# PCB_LEDs_GPIO_servicios_2021-05-17.net
KiCad netlist of a schematic drawn in EasyEDA
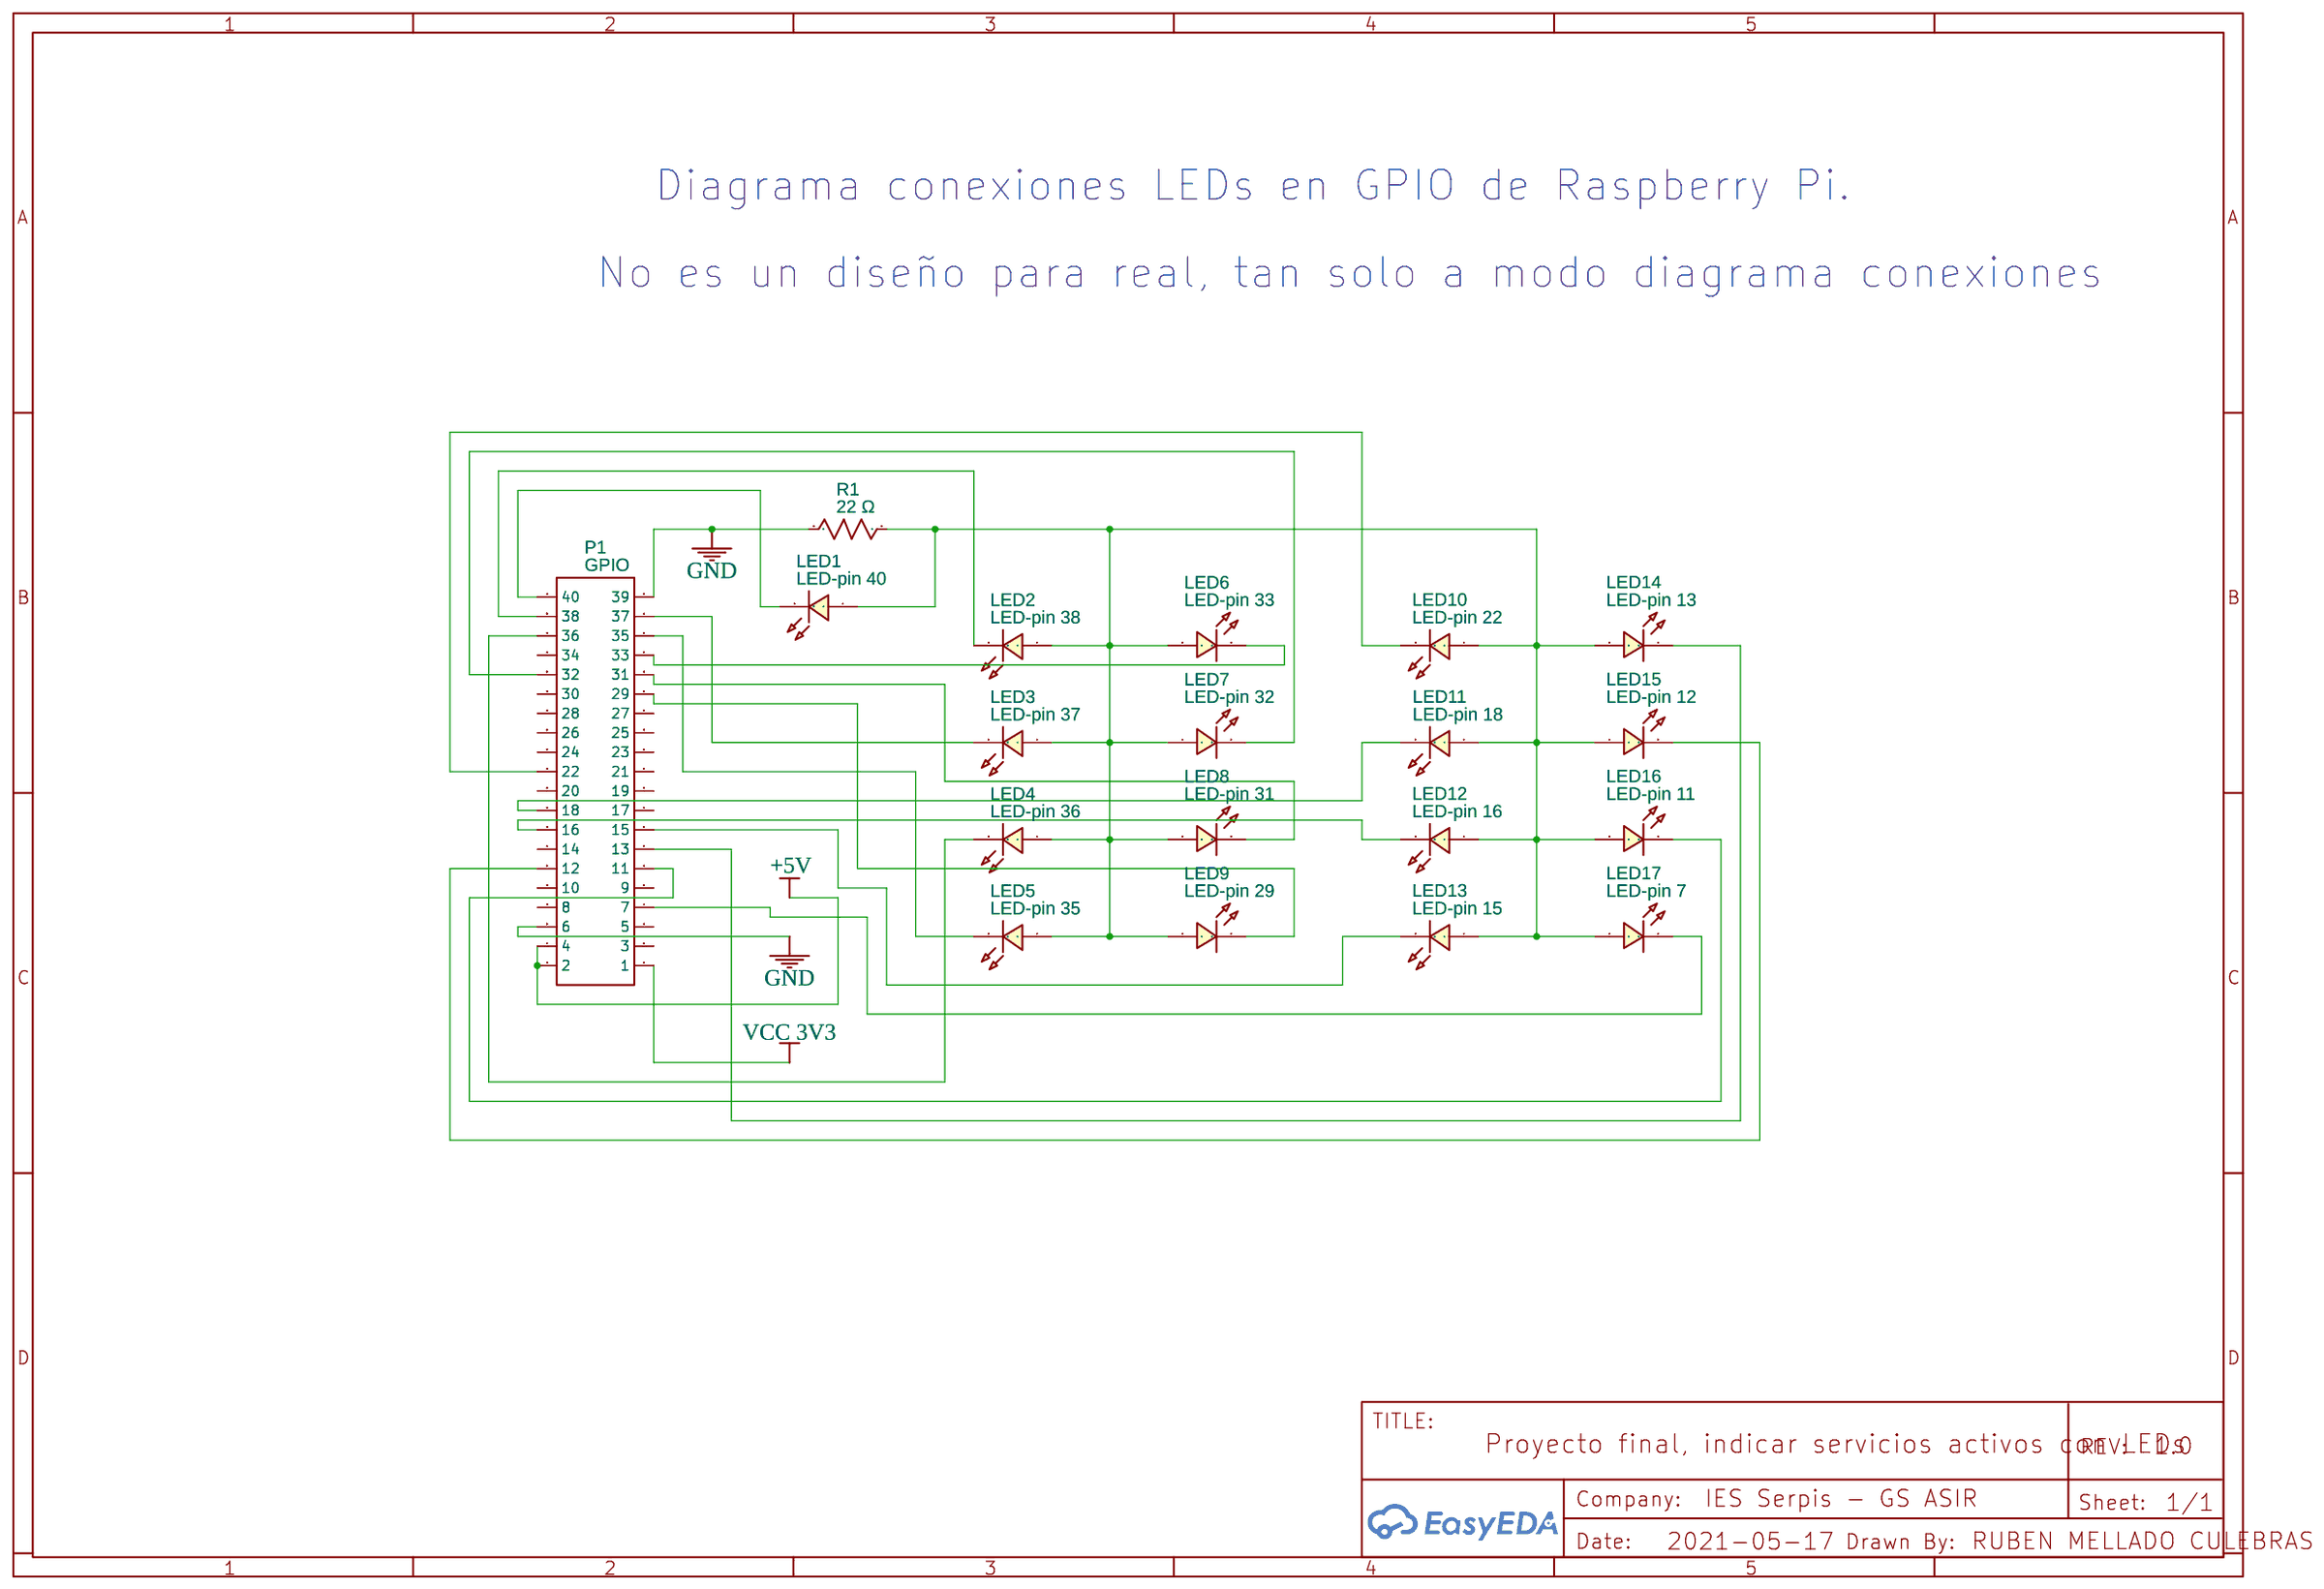
[diagram p0: schematic sheet]

(export (version "E")
  (design (tool "Eeschema 10.0.6"))
  (components
    (comp (ref "LED1")
      (value "LED-pin 40")
      (fields
        (field (name "BOM_Manufacturer Part") "19-217/R6C-AL1M2VY/3T")
        (field (name "BOM_Supplier Part") "C72044")
      )
      (libsource (lib "") (part "LED-0603_R_1"))
    )
    (comp (ref "LED2")
      (value "LED-pin 38")
      (fields
        (field (name "BOM_Manufacturer Part") "19-217/R6C-AL1M2VY/3T")
        (field (name "BOM_Supplier Part") "C72044")
      )
      (libsource (lib "") (part "LED-0603_R_1"))
    )
    (comp (ref "LED3")
      (value "LED-pin 37")
      (fields
        (field (name "BOM_Manufacturer Part") "19-217/R6C-AL1M2VY/3T")
        (field (name "BOM_Supplier Part") "C72044")
      )
      (libsource (lib "") (part "LED-0603_R_1"))
    )
    (comp (ref "LED4")
      (value "LED-pin 36")
      (fields
        (field (name "BOM_Manufacturer Part") "19-217/R6C-AL1M2VY/3T")
        (field (name "BOM_Supplier Part") "C72044")
      )
      (libsource (lib "") (part "LED-0603_R_1"))
    )
    (comp (ref "LED5")
      (value "LED-pin 35")
      (fields
        (field (name "BOM_Manufacturer Part") "19-217/R6C-AL1M2VY/3T")
        (field (name "BOM_Supplier Part") "C72044")
      )
      (libsource (lib "") (part "LED-0603_R_1"))
    )
    (comp (ref "LED6")
      (value "LED-pin 33")
      (fields
        (field (name "BOM_Manufacturer Part") "19-217/R6C-AL1M2VY/3T")
        (field (name "BOM_Supplier Part") "C72044")
      )
      (libsource (lib "") (part "LED-0603_R"))
    )
    (comp (ref "LED7")
      (value "LED-pin 32")
      (fields
        (field (name "BOM_Manufacturer Part") "19-217/R6C-AL1M2VY/3T")
        (field (name "BOM_Supplier Part") "C72044")
      )
      (libsource (lib "") (part "LED-0603_R"))
    )
    (comp (ref "LED8")
      (value "LED-pin 31")
      (fields
        (field (name "BOM_Manufacturer Part") "19-217/R6C-AL1M2VY/3T")
        (field (name "BOM_Supplier Part") "C72044")
      )
      (libsource (lib "") (part "LED-0603_R"))
    )
    (comp (ref "LED9")
      (value "LED-pin 29")
      (fields
        (field (name "BOM_Manufacturer Part") "19-217/R6C-AL1M2VY/3T")
        (field (name "BOM_Supplier Part") "C72044")
      )
      (libsource (lib "") (part "LED-0603_R"))
    )
    (comp (ref "LED10")
      (value "LED-pin 22")
      (fields
        (field (name "BOM_Manufacturer Part") "19-217/R6C-AL1M2VY/3T")
        (field (name "BOM_Supplier Part") "C72044")
      )
      (libsource (lib "") (part "LED-0603_R_1"))
    )
    (comp (ref "LED11")
      (value "LED-pin 18")
      (fields
        (field (name "BOM_Manufacturer Part") "19-217/R6C-AL1M2VY/3T")
        (field (name "BOM_Supplier Part") "C72044")
      )
      (libsource (lib "") (part "LED-0603_R_1"))
    )
    (comp (ref "LED12")
      (value "LED-pin 16")
      (fields
        (field (name "BOM_Manufacturer Part") "19-217/R6C-AL1M2VY/3T")
        (field (name "BOM_Supplier Part") "C72044")
      )
      (libsource (lib "") (part "LED-0603_R_1"))
    )
    (comp (ref "LED13")
      (value "LED-pin 15")
      (fields
        (field (name "BOM_Manufacturer Part") "19-217/R6C-AL1M2VY/3T")
        (field (name "BOM_Supplier Part") "C72044")
      )
      (libsource (lib "") (part "LED-0603_R_1"))
    )
    (comp (ref "LED14")
      (value "LED-pin 13")
      (fields
        (field (name "BOM_Manufacturer Part") "19-217/R6C-AL1M2VY/3T")
        (field (name "BOM_Supplier Part") "C72044")
      )
      (libsource (lib "") (part "LED-0603_R"))
    )
    (comp (ref "LED15")
      (value "LED-pin 12")
      (fields
        (field (name "BOM_Manufacturer Part") "19-217/R6C-AL1M2VY/3T")
        (field (name "BOM_Supplier Part") "C72044")
      )
      (libsource (lib "") (part "LED-0603_R"))
    )
    (comp (ref "LED16")
      (value "LED-pin 11")
      (fields
        (field (name "BOM_Manufacturer Part") "19-217/R6C-AL1M2VY/3T")
        (field (name "BOM_Supplier Part") "C72044")
      )
      (libsource (lib "") (part "LED-0603_R"))
    )
    (comp (ref "LED17")
      (value "LED-pin 7")
      (fields
        (field (name "BOM_Manufacturer Part") "19-217/R6C-AL1M2VY/3T")
        (field (name "BOM_Supplier Part") "C72044")
      )
      (libsource (lib "") (part "LED-0603_R"))
    )
    (comp (ref "P1")
      (value "GPIO")
      (fields
        (field (name "BOM_Manufacturer Part") "IDC Box 2X20 2.54MM")
        (field (name "BOM_Supplier Part") "C9138")
      )
      (libsource (lib "") (part "HDR-IDC-2.54-2X20P"))
    )
    (comp (ref "R1") (value "22 Ω") (libsource (lib "") (part "R_0603_US")))
  )
  (nets
    (net (code "1") (name "+5V") (class "Default")
      (node (ref "P1") (pin "2") (pinfunction "2_2") (pintype "unspecified"))
      (node (ref "P1") (pin "4") (pinfunction "4_4") (pintype "unspecified"))
    )
    (net (code "2") (name "GND") (class "Default")
      (node (ref "P1") (pin "39") (pinfunction "39_39") (pintype "unspecified"))
      (node (ref "P1") (pin "6") (pinfunction "6_6") (pintype "unspecified"))
      (node (ref "R1") (pin "1") (pinfunction "1_1") (pintype "unspecified"))
    )
    (net (code "3") (name "Net-(LED1-Pad1)") (class "Default")
      (node (ref "LED1") (pin "1") (pinfunction "1_1") (pintype "unspecified"))
      (node (ref "LED10") (pin "1") (pinfunction "1_1") (pintype "unspecified"))
      (node (ref "LED11") (pin "1") (pinfunction "1_1") (pintype "unspecified"))
      (node (ref "LED12") (pin "1") (pinfunction "1_1") (pintype "unspecified"))
      (node (ref "LED13") (pin "1") (pinfunction "1_1") (pintype "unspecified"))
      (node (ref "LED14") (pin "1") (pinfunction "1_1") (pintype "unspecified"))
      (node (ref "LED15") (pin "1") (pinfunction "1_1") (pintype "unspecified"))
      (node (ref "LED16") (pin "1") (pinfunction "1_1") (pintype "unspecified"))
      (node (ref "LED17") (pin "1") (pinfunction "1_1") (pintype "unspecified"))
      (node (ref "LED2") (pin "1") (pinfunction "1_1") (pintype "unspecified"))
      (node (ref "LED3") (pin "1") (pinfunction "1_1") (pintype "unspecified"))
      (node (ref "LED4") (pin "1") (pinfunction "1_1") (pintype "unspecified"))
      (node (ref "LED5") (pin "1") (pinfunction "1_1") (pintype "unspecified"))
      (node (ref "LED6") (pin "1") (pinfunction "1_1") (pintype "unspecified"))
      (node (ref "LED7") (pin "1") (pinfunction "1_1") (pintype "unspecified"))
      (node (ref "LED8") (pin "1") (pinfunction "1_1") (pintype "unspecified"))
      (node (ref "LED9") (pin "1") (pinfunction "1_1") (pintype "unspecified"))
      (node (ref "R1") (pin "2") (pinfunction "2_2") (pintype "unspecified"))
    )
    (net (code "4") (name "Net-(LED1-Pad2)") (class "Default")
      (node (ref "LED1") (pin "2") (pinfunction "2_2") (pintype "unspecified"))
      (node (ref "P1") (pin "40") (pinfunction "40_40") (pintype "unspecified"))
    )
    (net (code "5") (name "Net-(LED2-Pad2)") (class "Default")
      (node (ref "LED2") (pin "2") (pinfunction "2_2") (pintype "unspecified"))
      (node (ref "P1") (pin "38") (pinfunction "38_38") (pintype "unspecified"))
    )
    (net (code "6") (name "Net-(LED3-Pad2)") (class "Default")
      (node (ref "LED3") (pin "2") (pinfunction "2_2") (pintype "unspecified"))
      (node (ref "P1") (pin "37") (pinfunction "37_37") (pintype "unspecified"))
    )
    (net (code "7") (name "Net-(LED4-Pad2)") (class "Default")
      (node (ref "LED4") (pin "2") (pinfunction "2_2") (pintype "unspecified"))
      (node (ref "P1") (pin "36") (pinfunction "36_36") (pintype "unspecified"))
    )
    (net (code "8") (name "Net-(LED5-Pad2)") (class "Default")
      (node (ref "LED5") (pin "2") (pinfunction "2_2") (pintype "unspecified"))
      (node (ref "P1") (pin "35") (pinfunction "35_35") (pintype "unspecified"))
    )
    (net (code "9") (name "Net-(LED6-Pad2)") (class "Default")
      (node (ref "LED6") (pin "2") (pinfunction "2_2") (pintype "unspecified"))
      (node (ref "P1") (pin "33") (pinfunction "33_33") (pintype "unspecified"))
    )
    (net (code "10") (name "Net-(LED7-Pad2)") (class "Default")
      (node (ref "LED7") (pin "2") (pinfunction "2_2") (pintype "unspecified"))
      (node (ref "P1") (pin "32") (pinfunction "32_32") (pintype "unspecified"))
    )
    (net (code "11") (name "Net-(LED8-Pad2)") (class "Default")
      (node (ref "LED8") (pin "2") (pinfunction "2_2") (pintype "unspecified"))
      (node (ref "P1") (pin "31") (pinfunction "31_31") (pintype "unspecified"))
    )
    (net (code "12") (name "Net-(LED9-Pad2)") (class "Default")
      (node (ref "LED9") (pin "2") (pinfunction "2_2") (pintype "unspecified"))
      (node (ref "P1") (pin "29") (pinfunction "29_29") (pintype "unspecified"))
    )
    (net (code "13") (name "Net-(LED10-Pad2)") (class "Default")
      (node (ref "LED10") (pin "2") (pinfunction "2_2") (pintype "unspecified"))
      (node (ref "P1") (pin "22") (pinfunction "22_22") (pintype "unspecified"))
    )
    (net (code "14") (name "Net-(LED11-Pad2)") (class "Default")
      (node (ref "LED11") (pin "2") (pinfunction "2_2") (pintype "unspecified"))
      (node (ref "P1") (pin "18") (pinfunction "18_18") (pintype "unspecified"))
    )
    (net (code "15") (name "Net-(LED12-Pad2)") (class "Default")
      (node (ref "LED12") (pin "2") (pinfunction "2_2") (pintype "unspecified"))
      (node (ref "P1") (pin "16") (pinfunction "16_16") (pintype "unspecified"))
    )
    (net (code "16") (name "Net-(LED13-Pad2)") (class "Default")
      (node (ref "LED13") (pin "2") (pinfunction "2_2") (pintype "unspecified"))
      (node (ref "P1") (pin "15") (pinfunction "15_15") (pintype "unspecified"))
    )
    (net (code "17") (name "Net-(LED14-Pad2)") (class "Default")
      (node (ref "LED14") (pin "2") (pinfunction "2_2") (pintype "unspecified"))
      (node (ref "P1") (pin "13") (pinfunction "13_13") (pintype "unspecified"))
    )
    (net (code "18") (name "Net-(LED15-Pad2)") (class "Default")
      (node (ref "LED15") (pin "2") (pinfunction "2_2") (pintype "unspecified"))
      (node (ref "P1") (pin "12") (pinfunction "12_12") (pintype "unspecified"))
    )
    (net (code "19") (name "Net-(LED16-Pad2)") (class "Default")
      (node (ref "LED16") (pin "2") (pinfunction "2_2") (pintype "unspecified"))
      (node (ref "P1") (pin "11") (pinfunction "11_11") (pintype "unspecified"))
    )
    (net (code "20") (name "Net-(LED17-Pad2)") (class "Default")
      (node (ref "LED17") (pin "2") (pinfunction "2_2") (pintype "unspecified"))
      (node (ref "P1") (pin "7") (pinfunction "7_7") (pintype "unspecified"))
    )
    (net (code "21") (name "VCC 3V3") (class "Default")
      (node (ref "P1") (pin "1") (pinfunction "1_1") (pintype "unspecified"))
    )
    (net (code "22") (name "unconnected-(P1-Pad3)") (class "Default")
      (node (ref "P1") (pin "3") (pinfunction "3_3") (pintype "unspecified"))
    )
    (net (code "23") (name "unconnected-(P1-Pad5)") (class "Default")
      (node (ref "P1") (pin "5") (pinfunction "5_5") (pintype "unspecified"))
    )
    (net (code "24") (name "unconnected-(P1-Pad8)") (class "Default")
      (node (ref "P1") (pin "8") (pinfunction "8_8") (pintype "unspecified"))
    )
    (net (code "25") (name "unconnected-(P1-Pad9)") (class "Default")
      (node (ref "P1") (pin "9") (pinfunction "9_9") (pintype "unspecified"))
    )
    (net (code "26") (name "unconnected-(P1-Pad10)") (class "Default")
      (node (ref "P1") (pin "10") (pinfunction "10_10") (pintype "unspecified"))
    )
    (net (code "27") (name "unconnected-(P1-Pad14)") (class "Default")
      (node (ref "P1") (pin "14") (pinfunction "14_14") (pintype "unspecified"))
    )
    (net (code "28") (name "unconnected-(P1-Pad17)") (class "Default")
      (node (ref "P1") (pin "17") (pinfunction "17_17") (pintype "unspecified"))
    )
    (net (code "29") (name "unconnected-(P1-Pad19)") (class "Default")
      (node (ref "P1") (pin "19") (pinfunction "19_19") (pintype "unspecified"))
    )
    (net (code "30") (name "unconnected-(P1-Pad20)") (class "Default")
      (node (ref "P1") (pin "20") (pinfunction "20_20") (pintype "unspecified"))
    )
    (net (code "31") (name "unconnected-(P1-Pad21)") (class "Default")
      (node (ref "P1") (pin "21") (pinfunction "21_21") (pintype "unspecified"))
    )
    (net (code "32") (name "unconnected-(P1-Pad23)") (class "Default")
      (node (ref "P1") (pin "23") (pinfunction "23_23") (pintype "unspecified"))
    )
    (net (code "33") (name "unconnected-(P1-Pad24)") (class "Default")
      (node (ref "P1") (pin "24") (pinfunction "24_24") (pintype "unspecified"))
    )
    (net (code "34") (name "unconnected-(P1-Pad25)") (class "Default")
      (node (ref "P1") (pin "25") (pinfunction "25_25") (pintype "unspecified"))
    )
    (net (code "35") (name "unconnected-(P1-Pad26)") (class "Default")
      (node (ref "P1") (pin "26") (pinfunction "26_26") (pintype "unspecified"))
    )
    (net (code "36") (name "unconnected-(P1-Pad27)") (class "Default")
      (node (ref "P1") (pin "27") (pinfunction "27_27") (pintype "unspecified"))
    )
    (net (code "37") (name "unconnected-(P1-Pad28)") (class "Default")
      (node (ref "P1") (pin "28") (pinfunction "28_28") (pintype "unspecified"))
    )
    (net (code "38") (name "unconnected-(P1-Pad30)") (class "Default")
      (node (ref "P1") (pin "30") (pinfunction "30_30") (pintype "unspecified"))
    )
    (net (code "39") (name "unconnected-(P1-Pad34)") (class "Default")
      (node (ref "P1") (pin "34") (pinfunction "34_34") (pintype "unspecified"))
    )
  )
)
